# Buck_Converter_3_3V.net
KiCad netlist of a schematic drawn in Altium Designer
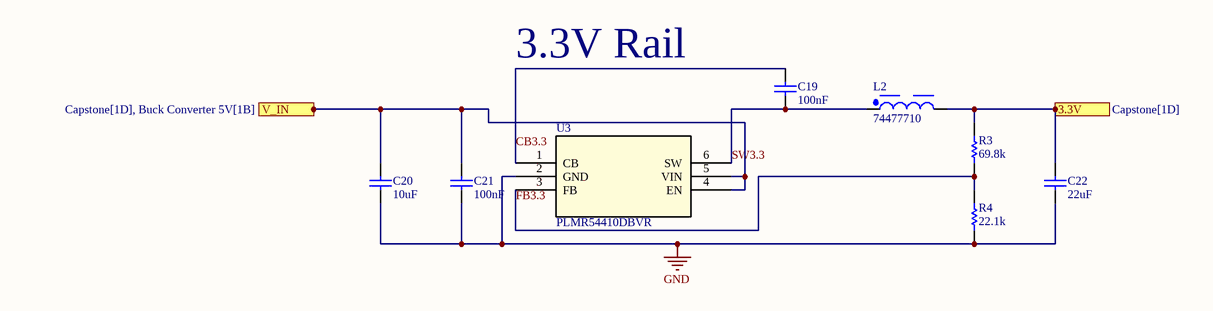
[diagram p0: Buck Converter 3.3V.SchDoc]

(export (version "E")
  (design (tool "Eeschema 10.0.6"))
  (components
    (comp (ref "C19")
      (value "100nF")
      (footprint "CAPC2013X135X45LL10T25")
      (description "Chip Capacitor, 4.7 uF, +/- 10%, 16 V, -55 to 85 degC, 0805 (2012 Metric), RoHS, Tape and Reel")
      (fields (field (name "TOLERANCE") "10%") (field (name "PARTNUMBER") "GRM21BR61C475KA88L"))
      (libsource (lib "Altium Content Vault") (part "CAP-NP-2"))
    )
    (comp (ref "C20")
      (value "10uF")
      (footprint "CAPC2013X135X45LL10T25")
      (description "Chip Capacitor, 4.7 uF, +/- 10%, 16 V, -55 to 85 degC, 0805 (2012 Metric), RoHS, Tape and Reel")
      (fields (field (name "TOLERANCE") "10%") (field (name "PARTNUMBER") "GRM21BR61C475KA88L"))
      (libsource (lib "Altium Content Vault") (part "CAP-NP-2"))
    )
    (comp (ref "C21")
      (value "100nF")
      (footprint "CAPC2013X135X45LL10T25")
      (description "Chip Capacitor, 4.7 uF, +/- 10%, 16 V, -55 to 85 degC, 0805 (2012 Metric), RoHS, Tape and Reel")
      (fields (field (name "TOLERANCE") "10%") (field (name "PARTNUMBER") "GRM21BR61C475KA88L"))
      (libsource (lib "Altium Content Vault") (part "CAP-NP-2"))
    )
    (comp (ref "C22")
      (value "22uF")
      (footprint "CAPC2013X135X45LL10T25")
      (description "Chip Capacitor, 4.7 uF, +/- 10%, 16 V, -55 to 85 degC, 0805 (2012 Metric), RoHS, Tape and Reel")
      (fields (field (name "TOLERANCE") "10%") (field (name "PARTNUMBER") "GRM21BR61C475KA88L"))
      (libsource (lib "Altium Content Vault") (part "CAP-NP-2"))
    )
    (comp (ref "L2")
      (value "74477710")
      (footprint "WE-PD_7345")
      (fields (field (name "TOLERANCE") "20%"))
      (libsource (lib "Altium Content Vault") (part "Inductor - 2"))
    )
    (comp (ref "R3")
      (value "69.8k")
      (footprint "RESC1608X55X25ML10T15")
      (description "Chip Resistor, 0 Ohm, +/- 5%, 0.1 W, -55 to 155 degC, 0603 (1608 Metric), RoHS, Tape and Reel")
      (fields (field (name "TOLERANCE") "5%") (field (name "MANUFACTURER") "Yageo"))
      (libsource (lib "Altium Content Vault") (part "RES-2"))
    )
    (comp (ref "R4")
      (value "22.1k")
      (footprint "RESC1608X55X25ML10T15")
      (description "Chip Resistor, 0 Ohm, +/- 5%, 0.1 W, -55 to 155 degC, 0603 (1608 Metric), RoHS, Tape and Reel")
      (fields (field (name "TOLERANCE") "5%") (field (name "MANUFACTURER") "Yageo"))
      (libsource (lib "Altium Content Vault") (part "RES-2"))
    )
    (comp (ref "U3")
      (value "PLMR54410DBVR")
      (footprint "U_SOT-23_TEX")
      (description "No Description Available")
      (libsource (lib "PLMR54410DBVR") (part "PLMR54410DBVR"))
    )
  )
  (nets
    (net (code "1") (name "/3.3V") (class "Default")
      (node (ref "C22") (pin "2") (pinfunction "2_2") (pintype "passive"))
      (node (ref "L2") (pin "2") (pinfunction "2_2") (pintype "passive"))
      (node (ref "R3") (pin "2") (pinfunction "2_2") (pintype "passive"))
    )
    (net (code "2") (name "/CB3.3") (class "Default")
      (node (ref "C19") (pin "2") (pinfunction "2_2") (pintype "passive"))
      (node (ref "U3") (pin "1") (pinfunction "CB_1") (pintype "power_in"))
    )
    (net (code "3") (name "/FB3.3") (class "Default")
      (node (ref "R3") (pin "1") (pinfunction "1_1") (pintype "passive"))
      (node (ref "R4") (pin "2") (pinfunction "2_2") (pintype "passive"))
      (node (ref "U3") (pin "3") (pinfunction "FB_3") (pintype "passive"))
    )
    (net (code "4") (name "/SW3.3") (class "Default")
      (node (ref "C19") (pin "1") (pinfunction "1_1") (pintype "passive"))
      (node (ref "L2") (pin "1") (pinfunction "1_1") (pintype "passive"))
      (node (ref "U3") (pin "6") (pinfunction "SW_6") (pintype "power_in"))
    )
    (net (code "5") (name "/V_IN") (class "Default")
      (node (ref "C20") (pin "2") (pinfunction "2_2") (pintype "passive"))
      (node (ref "C21") (pin "2") (pinfunction "2_2") (pintype "passive"))
      (node (ref "U3") (pin "4") (pinfunction "EN_4") (pintype "passive"))
      (node (ref "U3") (pin "5") (pinfunction "VIN_5") (pintype "passive"))
    )
    (net (code "6") (name "GND") (class "Default")
      (node (ref "C20") (pin "1") (pinfunction "1_1") (pintype "passive"))
      (node (ref "C21") (pin "1") (pinfunction "1_1") (pintype "passive"))
      (node (ref "C22") (pin "1") (pinfunction "1_1") (pintype "passive"))
      (node (ref "R4") (pin "1") (pinfunction "1_1") (pintype "passive"))
      (node (ref "U3") (pin "2") (pinfunction "GND_2") (pintype "passive"))
    )
  )
)
